# si1133-breakout.net
KiCad netlist of a schematic drawn in EAGLE
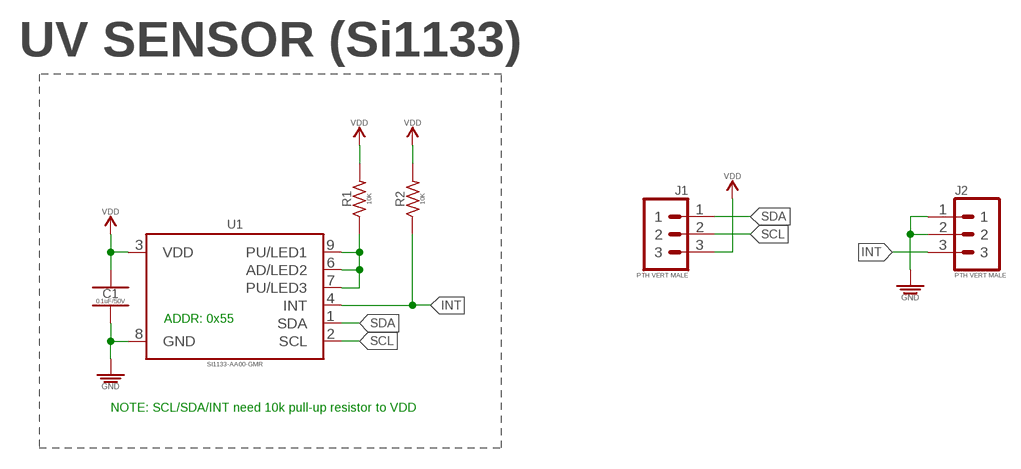
[diagram p0: schematic, sheet 1]

(export (version "E")
  (design (tool "Eeschema 10.0.6"))
  (components
    (comp (ref "C1")
      (value "0.1uF/50V")
      (footprint "eagle-import:CAPC1005X55_SMD-0402")
      (fields (field (name "MFR") "TDK Corporation") (field (name "MPN") "C1005X7R1H104K050BE"))
      (libsource (lib "eagle-import") (part "0.1UF_SMD-0402_50V-10%"))
    )
    (comp (ref "J1")
      (value "PTH VERT MALE")
      (footprint "eagle-import:HDRV3W64P254_1X3_762X254X838B")
      (fields (field (name "MFR") "Sullins Connector Solutions") (field (name "MPN") "PEC03SAAN"))
      (libsource (lib "eagle-import") (part "1X03_PTH_VERT_MALE_2.54MM"))
    )
    (comp (ref "J2")
      (value "PTH VERT MALE")
      (footprint "eagle-import:HDRV3W64P254_1X3_762X254X838B")
      (fields (field (name "MFR") "Sullins Connector Solutions") (field (name "MPN") "PEC03SAAN"))
      (libsource (lib "eagle-import") (part "1X03_PTH_VERT_MALE_2.54MM"))
    )
    (comp (ref "R1")
      (value "10K")
      (footprint "eagle-import:RESC1005X35_SMD-0402")
      (fields (field (name "MFR") "Yageo") (field (name "MPN") "RC0402JR-0710KP"))
      (libsource (lib "eagle-import") (part "10KΩ_SMD-0402_1/16W-5%"))
    )
    (comp (ref "R2")
      (value "10K")
      (footprint "eagle-import:RESC1005X35_SMD-0402")
      (fields (field (name "MFR") "Yageo") (field (name "MPN") "RC0402JR-0710KP"))
      (libsource (lib "eagle-import") (part "10KΩ_SMD-0402_1/16W-5%"))
    )
    (comp (ref "U1")
      (value "SI1133-AA00-GMR")
      (footprint "eagle-import:QFN50P200X200X75-10N")
      (fields (field (name "MFR") "Silicon Labs"))
      (libsource (lib "eagle-import") (part "SI1133"))
    )
  )
  (nets
    (net (code "1") (name "GND") (class "Default")
      (node (ref "C1") (pin "2") (pinfunction "2_2") (pintype "passive"))
      (node (ref "J2") (pin "1") (pinfunction "1_1") (pintype "passive"))
      (node (ref "J2") (pin "2") (pinfunction "2_2") (pintype "passive"))
      (node (ref "U1") (pin "8") (pinfunction "GND_8") (pintype "power_in"))
    )
    (net (code "2") (name "INT") (class "Default")
      (node (ref "J2") (pin "3") (pinfunction "3_3") (pintype "passive"))
      (node (ref "R2") (pin "1") (pinfunction "1_1") (pintype "passive"))
      (node (ref "U1") (pin "4") (pinfunction "INT_4") (pintype "bidirectional"))
    )
    (net (code "3") (name "Net-(U1-AD{slash}LED2)") (class "Default")
      (node (ref "R1") (pin "1") (pinfunction "1_1") (pintype "passive"))
      (node (ref "U1") (pin "6") (pinfunction "AD/LED2_6") (pintype "output"))
      (node (ref "U1") (pin "7") (pinfunction "PU/LED3_7") (pintype "output"))
      (node (ref "U1") (pin "9") (pinfunction "PU/LED1_9") (pintype "output"))
    )
    (net (code "4") (name "SCL") (class "Default")
      (node (ref "J1") (pin "2") (pinfunction "2_2") (pintype "passive"))
      (node (ref "U1") (pin "2") (pinfunction "SCL_2") (pintype "bidirectional"))
    )
    (net (code "5") (name "SDA") (class "Default")
      (node (ref "J1") (pin "1") (pinfunction "1_1") (pintype "passive"))
      (node (ref "U1") (pin "1") (pinfunction "SDA_1") (pintype "bidirectional"))
    )
    (net (code "6") (name "VDD") (class "Default")
      (node (ref "C1") (pin "1") (pinfunction "1_1") (pintype "passive"))
      (node (ref "J1") (pin "3") (pinfunction "3_3") (pintype "passive"))
      (node (ref "R1") (pin "2") (pinfunction "2_2") (pintype "passive"))
      (node (ref "R2") (pin "2") (pinfunction "2_2") (pintype "passive"))
      (node (ref "U1") (pin "3") (pinfunction "VDD_3") (pintype "power_in"))
    )
  )
)
